# PowerOutCurrentMonitor.net
KiCad netlist of a schematic drawn in Altium Designer
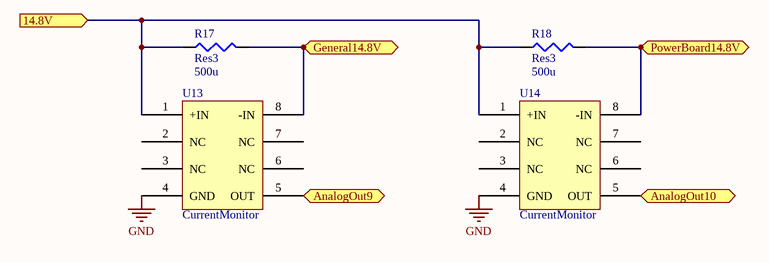
[diagram p0: PowerOutCurrentMonitor.SchDoc]

(export (version "E")
  (design (tool "Eeschema 10.0.6"))
  (components
    (comp (ref "R17")
      (value "Res3")
      (footprint "Resistor05MOHM")
      (description "Resistor")
      (fields (field (name "ALTIUM_VALUE") "500u") (field (name "PUBLISHER") "Altium Limited"))
      (libsource (lib "Miscellaneous Devices") (part "Res3"))
    )
    (comp (ref "R18")
      (value "Res3")
      (footprint "Resistor05MOHM")
      (description "Resistor")
      (fields (field (name "ALTIUM_VALUE") "500u") (field (name "PUBLISHER") "Altium Limited"))
      (libsource (lib "Miscellaneous Devices") (part "Res3"))
    )
    (comp (ref "U13")
      (value "CurrentMonitor")
      (footprint "AD8217")
      (libsource (lib "AD8217") (part "AD8217"))
    )
    (comp (ref "U14")
      (value "CurrentMonitor")
      (footprint "AD8217")
      (libsource (lib "AD8217") (part "AD8217"))
    )
  )
  (nets
    (net (code "1") (name "/14.8V") (class "Default")
      (node (ref "R17") (pin "1") (pinfunction "1_1") (pintype "passive"))
      (node (ref "R18") (pin "1") (pinfunction "1_1") (pintype "passive"))
      (node (ref "U13") (pin "1") (pinfunction "+IN_1") (pintype "passive"))
      (node (ref "U14") (pin "1") (pinfunction "+IN_1") (pintype "passive"))
    )
    (net (code "2") (name "/AnalogOut9") (class "Default")
      (node (ref "U13") (pin "5") (pinfunction "OUT_5") (pintype "passive"))
    )
    (net (code "3") (name "/AnalogOut10") (class "Default")
      (node (ref "U14") (pin "5") (pinfunction "OUT_5") (pintype "passive"))
    )
    (net (code "4") (name "/General14.8V") (class "Default")
      (node (ref "R17") (pin "2") (pinfunction "2_2") (pintype "passive"))
      (node (ref "U13") (pin "8") (pinfunction "-IN_8") (pintype "passive"))
    )
    (net (code "5") (name "/PowerBoard14.8V") (class "Default")
      (node (ref "R18") (pin "2") (pinfunction "2_2") (pintype "passive"))
      (node (ref "U14") (pin "8") (pinfunction "-IN_8") (pintype "passive"))
    )
    (net (code "6") (name "GND") (class "Default")
      (node (ref "U13") (pin "4") (pinfunction "GND_4") (pintype "passive"))
      (node (ref "U14") (pin "4") (pinfunction "GND_4") (pintype "passive"))
    )
    (net (code "7") (name "unconnected-(U13-NC-Pad2)") (class "Default")
      (node (ref "U13") (pin "2") (pinfunction "NC_2") (pintype "passive"))
    )
    (net (code "8") (name "unconnected-(U13-NC-Pad3)") (class "Default")
      (node (ref "U13") (pin "3") (pinfunction "NC_3") (pintype "passive"))
    )
    (net (code "9") (name "unconnected-(U13-NC-Pad6)") (class "Default")
      (node (ref "U13") (pin "6") (pinfunction "NC_6") (pintype "passive"))
    )
    (net (code "10") (name "unconnected-(U13-NC-Pad7)") (class "Default")
      (node (ref "U13") (pin "7") (pinfunction "NC_7") (pintype "passive"))
    )
    (net (code "11") (name "unconnected-(U14-NC-Pad2)") (class "Default")
      (node (ref "U14") (pin "2") (pinfunction "NC_2") (pintype "passive"))
    )
    (net (code "12") (name "unconnected-(U14-NC-Pad3)") (class "Default")
      (node (ref "U14") (pin "3") (pinfunction "NC_3") (pintype "passive"))
    )
    (net (code "13") (name "unconnected-(U14-NC-Pad6)") (class "Default")
      (node (ref "U14") (pin "6") (pinfunction "NC_6") (pintype "passive"))
    )
    (net (code "14") (name "unconnected-(U14-NC-Pad7)") (class "Default")
      (node (ref "U14") (pin "7") (pinfunction "NC_7") (pintype "passive"))
    )
  )
)
